# greenshield.net
KiCad netlist of a schematic drawn in EAGLE
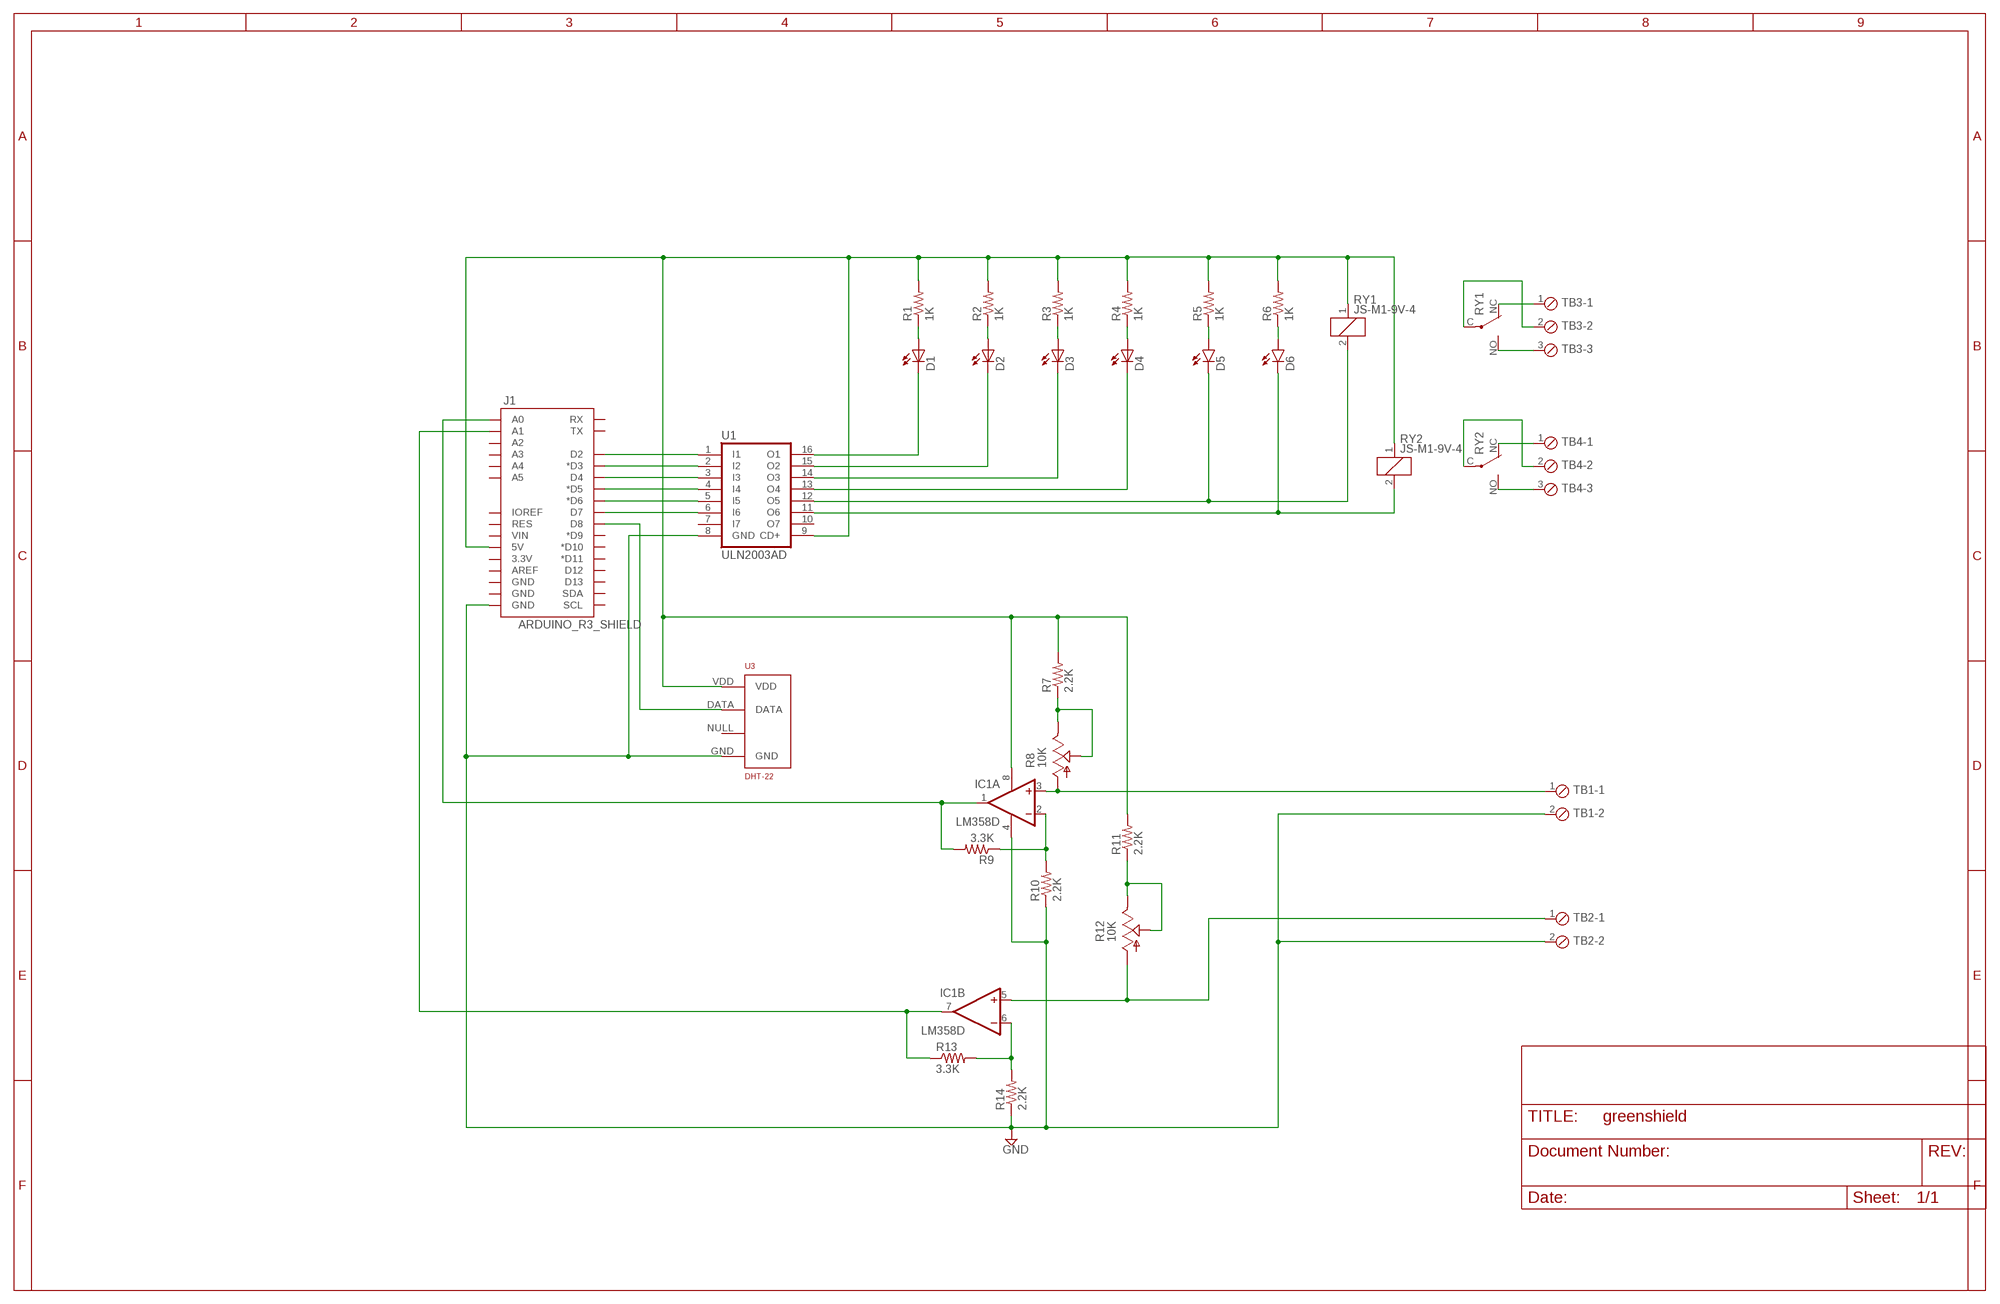
[diagram p0: schematic, sheet 1]

(export (version "E")
  (design (tool "Eeschema 10.0.6"))
  (components
    (comp (ref "D1")
      (value "LED3MM")
      (footprint "eagle-import:LED3MM")
      (libsource (lib "eagle-import") (part "led_LED3MM"))
    )
    (comp (ref "D2")
      (value "LED3MM")
      (footprint "eagle-import:LED3MM")
      (libsource (lib "eagle-import") (part "led_LED3MM"))
    )
    (comp (ref "D3")
      (value "LED3MM")
      (footprint "eagle-import:LED3MM")
      (libsource (lib "eagle-import") (part "led_LED3MM"))
    )
    (comp (ref "D4")
      (value "LED3MM")
      (footprint "eagle-import:LED3MM")
      (libsource (lib "eagle-import") (part "led_LED3MM"))
    )
    (comp (ref "D5")
      (value "LED3MM")
      (footprint "eagle-import:LED3MM")
      (libsource (lib "eagle-import") (part "LED3MM"))
    )
    (comp (ref "D6")
      (value "LED3MM")
      (footprint "eagle-import:LED3MM")
      (libsource (lib "eagle-import") (part "LED3MM"))
    )
    (comp (ref "IC1")
      (value "LM358D")
      (footprint "eagle-import:SO08")
      (libsource (lib "eagle-import") (part "LM358D"))
    )
    (comp (ref "J1")
      (value "ARDUINO_R3_SHIELD")
      (footprint "eagle-import:UNO_R3_SHIELD")
      (libsource (lib "eagle-import") (part "ARDUINO_R3_SHIELD"))
    )
    (comp (ref "R1")
      (value "1K")
      (footprint "eagle-import:0805")
      (libsource (lib "eagle-import") (part "RESISTOR0805-RES"))
    )
    (comp (ref "R2")
      (value "1K")
      (footprint "eagle-import:0805")
      (libsource (lib "eagle-import") (part "RESISTOR0805-RES"))
    )
    (comp (ref "R3")
      (value "1K")
      (footprint "eagle-import:0805")
      (libsource (lib "eagle-import") (part "RESISTOR0805-RES"))
    )
    (comp (ref "R4")
      (value "1K")
      (footprint "eagle-import:0805")
      (libsource (lib "eagle-import") (part "RESISTOR0805-RES"))
    )
    (comp (ref "R5")
      (value "1K")
      (footprint "eagle-import:0805")
      (libsource (lib "eagle-import") (part "RESISTOR0805-RES"))
    )
    (comp (ref "R6")
      (value "1K")
      (footprint "eagle-import:0805")
      (libsource (lib "eagle-import") (part "RESISTOR0805-RES"))
    )
    (comp (ref "R7")
      (value "2.2K")
      (footprint "eagle-import:0805")
      (libsource (lib "eagle-import") (part "RESISTOR0805-RES"))
    )
    (comp (ref "R8")
      (value "10K")
      (footprint "eagle-import:S64W")
      (libsource (lib "eagle-import") (part "TRIM_US-S64W"))
    )
    (comp (ref "R9")
      (value "3.3K")
      (footprint "eagle-import:0805")
      (libsource (lib "eagle-import") (part "RESISTOR0805-RES"))
    )
    (comp (ref "R10")
      (value "2.2K")
      (footprint "eagle-import:0805")
      (libsource (lib "eagle-import") (part "RESISTOR0805-RES"))
    )
    (comp (ref "R11")
      (value "2.2K")
      (footprint "eagle-import:0805")
      (libsource (lib "eagle-import") (part "RESISTOR0805-RES"))
    )
    (comp (ref "R12")
      (value "10K")
      (footprint "eagle-import:S64W")
      (libsource (lib "eagle-import") (part "TRIM_US-S64W"))
    )
    (comp (ref "R13")
      (value "3.3K")
      (footprint "eagle-import:0805")
      (libsource (lib "eagle-import") (part "RESISTOR0805-RES"))
    )
    (comp (ref "R14")
      (value "2.2K")
      (footprint "eagle-import:0805")
      (libsource (lib "eagle-import") (part "RESISTOR0805-RES"))
    )
    (comp (ref "RY1")
      (value "JS-M1-9V-4")
      (footprint "eagle-import:JS-M")
      (libsource (lib "eagle-import") (part "JS-M1-9V-4"))
    )
    (comp (ref "RY2")
      (value "JS-M1-9V-4")
      (footprint "eagle-import:JS-M")
      (libsource (lib "eagle-import") (part "JS-M1-9V-4"))
    )
    (comp (ref "TB1")
      (value "MPT2")
      (footprint "eagle-import:2POL254")
      (libsource (lib "eagle-import") (part "MPT2"))
    )
    (comp (ref "TB2")
      (value "MPT2")
      (footprint "eagle-import:2POL254")
      (libsource (lib "eagle-import") (part "MPT2"))
    )
    (comp (ref "TB3")
      (value "MPT3")
      (footprint "eagle-import:3POL254")
      (libsource (lib "eagle-import") (part "MPT3"))
    )
    (comp (ref "TB4")
      (value "MPT3")
      (footprint "eagle-import:3POL254")
      (libsource (lib "eagle-import") (part "MPT3"))
    )
    (comp (ref "U1")
      (value "ULN2003AD")
      (footprint "eagle-import:SO16")
      (libsource (lib "eagle-import") (part "ULN2003AD"))
    )
    (comp (ref "U3")
      (value "DHT-22")
      (footprint "eagle-import:RHT03_DHT-22")
      (libsource (lib "eagle-import") (part "RHT03_DHT-22_AM2302"))
    )
  )
  (nets
    (net (code "1") (name "GND") (class "Default")
      (node (ref "IC1") (pin "4") (pinfunction "V-_4") (pintype "power_in"))
      (node (ref "J1") (pin "GND@0") (pinfunction "GND_GND@0") (pintype "bidirectional"))
      (node (ref "R10") (pin "1") (pinfunction "1_1") (pintype "passive"))
      (node (ref "R14") (pin "1") (pinfunction "1_1") (pintype "passive"))
      (node (ref "TB1") (pin "2") (pinfunction "1_2") (pintype "passive"))
      (node (ref "TB2") (pin "2") (pinfunction "1_2") (pintype "passive"))
      (node (ref "U1") (pin "8") (pinfunction "GND_8") (pintype "power_in"))
      (node (ref "U3") (pin "GND") (pinfunction "GND_GND") (pintype "power_in"))
    )
    (net (code "2") (name "Net-(D1-C)") (class "Default")
      (node (ref "D1") (pin "K") (pinfunction "C_K") (pintype "passive"))
      (node (ref "U1") (pin "16") (pinfunction "O1_16") (pintype "open_collector"))
    )
    (net (code "3") (name "Net-(D1-PadA)") (class "Default")
      (node (ref "D1") (pin "A") (pinfunction "A_A") (pintype "passive"))
      (node (ref "R1") (pin "1") (pinfunction "1_1") (pintype "passive"))
    )
    (net (code "4") (name "Net-(D2-C)") (class "Default")
      (node (ref "D2") (pin "K") (pinfunction "C_K") (pintype "passive"))
      (node (ref "U1") (pin "15") (pinfunction "O2_15") (pintype "open_collector"))
    )
    (net (code "5") (name "Net-(D2-PadA)") (class "Default")
      (node (ref "D2") (pin "A") (pinfunction "A_A") (pintype "passive"))
      (node (ref "R2") (pin "1") (pinfunction "1_1") (pintype "passive"))
    )
    (net (code "6") (name "Net-(D3-C)") (class "Default")
      (node (ref "D3") (pin "K") (pinfunction "C_K") (pintype "passive"))
      (node (ref "U1") (pin "14") (pinfunction "O3_14") (pintype "open_collector"))
    )
    (net (code "7") (name "Net-(D3-PadA)") (class "Default")
      (node (ref "D3") (pin "A") (pinfunction "A_A") (pintype "passive"))
      (node (ref "R3") (pin "1") (pinfunction "1_1") (pintype "passive"))
    )
    (net (code "8") (name "Net-(D4-C)") (class "Default")
      (node (ref "D4") (pin "K") (pinfunction "C_K") (pintype "passive"))
      (node (ref "U1") (pin "13") (pinfunction "O4_13") (pintype "open_collector"))
    )
    (net (code "9") (name "Net-(D4-PadA)") (class "Default")
      (node (ref "D4") (pin "A") (pinfunction "A_A") (pintype "passive"))
      (node (ref "R4") (pin "1") (pinfunction "1_1") (pintype "passive"))
    )
    (net (code "10") (name "Net-(D5-C)") (class "Default")
      (node (ref "D5") (pin "K") (pinfunction "C_K") (pintype "passive"))
      (node (ref "RY1") (pin "2") (pinfunction "2_2") (pintype "passive"))
      (node (ref "U1") (pin "12") (pinfunction "O5_12") (pintype "open_collector"))
    )
    (net (code "11") (name "Net-(D5-PadA)") (class "Default")
      (node (ref "D5") (pin "A") (pinfunction "A_A") (pintype "passive"))
      (node (ref "R5") (pin "1") (pinfunction "1_1") (pintype "passive"))
    )
    (net (code "12") (name "Net-(D6-C)") (class "Default")
      (node (ref "D6") (pin "K") (pinfunction "C_K") (pintype "passive"))
      (node (ref "RY2") (pin "2") (pinfunction "2_2") (pintype "passive"))
      (node (ref "U1") (pin "11") (pinfunction "O6_11") (pintype "open_collector"))
    )
    (net (code "13") (name "Net-(D6-PadA)") (class "Default")
      (node (ref "D6") (pin "A") (pinfunction "A_A") (pintype "passive"))
      (node (ref "R6") (pin "1") (pinfunction "1_1") (pintype "passive"))
    )
    (net (code "14") (name "Net-(IC1A-+IN)") (class "Default")
      (node (ref "IC1") (pin "3") (pinfunction "+IN_3") (pintype "input"))
      (node (ref "R8") (pin "A") (pinfunction "A_A") (pintype "passive"))
      (node (ref "TB1") (pin "1") (pinfunction "1_1") (pintype "passive"))
    )
    (net (code "15") (name "Net-(IC1A--IN)") (class "Default")
      (node (ref "IC1") (pin "2") (pinfunction "-IN_2") (pintype "input"))
      (node (ref "R10") (pin "2") (pinfunction "2_2") (pintype "passive"))
      (node (ref "R9") (pin "1") (pinfunction "1_1") (pintype "passive"))
    )
    (net (code "16") (name "Net-(IC1A-OUT)") (class "Default")
      (node (ref "IC1") (pin "1") (pinfunction "OUT_1") (pintype "output"))
      (node (ref "J1") (pin "A0") (pinfunction "A0_A0") (pintype "bidirectional"))
      (node (ref "R9") (pin "2") (pinfunction "2_2") (pintype "passive"))
    )
    (net (code "17") (name "Net-(IC1B-+IN)") (class "Default")
      (node (ref "IC1") (pin "5") (pinfunction "+IN_5") (pintype "input"))
      (node (ref "R12") (pin "A") (pinfunction "A_A") (pintype "passive"))
      (node (ref "TB2") (pin "1") (pinfunction "1_1") (pintype "passive"))
    )
    (net (code "18") (name "Net-(IC1B--IN)") (class "Default")
      (node (ref "IC1") (pin "6") (pinfunction "-IN_6") (pintype "input"))
      (node (ref "R13") (pin "2") (pinfunction "2_2") (pintype "passive"))
      (node (ref "R14") (pin "2") (pinfunction "2_2") (pintype "passive"))
    )
    (net (code "19") (name "Net-(IC1B-OUT)") (class "Default")
      (node (ref "IC1") (pin "7") (pinfunction "OUT_7") (pintype "output"))
      (node (ref "J1") (pin "A1") (pinfunction "A1_A1") (pintype "bidirectional"))
      (node (ref "R13") (pin "1") (pinfunction "1_1") (pintype "passive"))
    )
    (net (code "20") (name "Net-(IC1C-V+)") (class "Default")
      (node (ref "IC1") (pin "8") (pinfunction "V+_8") (pintype "power_in"))
      (node (ref "J1") (pin "5V") (pinfunction "5V_5V") (pintype "bidirectional"))
      (node (ref "R1") (pin "2") (pinfunction "2_2") (pintype "passive"))
      (node (ref "R11") (pin "2") (pinfunction "2_2") (pintype "passive"))
      (node (ref "R2") (pin "2") (pinfunction "2_2") (pintype "passive"))
      (node (ref "R3") (pin "2") (pinfunction "2_2") (pintype "passive"))
      (node (ref "R4") (pin "2") (pinfunction "2_2") (pintype "passive"))
      (node (ref "R5") (pin "2") (pinfunction "2_2") (pintype "passive"))
      (node (ref "R6") (pin "2") (pinfunction "2_2") (pintype "passive"))
      (node (ref "R7") (pin "2") (pinfunction "2_2") (pintype "passive"))
      (node (ref "RY1") (pin "1") (pinfunction "1_1") (pintype "passive"))
      (node (ref "RY2") (pin "1") (pinfunction "1_1") (pintype "passive"))
      (node (ref "U1") (pin "9") (pinfunction "CD+_9") (pintype "passive"))
      (node (ref "U3") (pin "VDD") (pinfunction "VDD_VDD") (pintype "power_in"))
    )
    (net (code "21") (name "Net-(J1-*D3)") (class "Default")
      (node (ref "J1") (pin "D3") (pinfunction "*D3_D3") (pintype "bidirectional"))
      (node (ref "U1") (pin "2") (pinfunction "I2_2") (pintype "input"))
    )
    (net (code "22") (name "Net-(J1-*D5)") (class "Default")
      (node (ref "J1") (pin "D5") (pinfunction "*D5_D5") (pintype "bidirectional"))
      (node (ref "U1") (pin "4") (pinfunction "I4_4") (pintype "input"))
    )
    (net (code "23") (name "Net-(J1-*D6)") (class "Default")
      (node (ref "J1") (pin "D6") (pinfunction "*D6_D6") (pintype "bidirectional"))
      (node (ref "U1") (pin "5") (pinfunction "I5_5") (pintype "input"))
    )
    (net (code "24") (name "Net-(J1-PadD8)") (class "Default")
      (node (ref "J1") (pin "D8") (pinfunction "D8_D8") (pintype "bidirectional"))
      (node (ref "U3") (pin "DATA") (pinfunction "DATA_DATA") (pintype "bidirectional"))
    )
    (net (code "25") (name "Net-(R7-Pad1)") (class "Default")
      (node (ref "R7") (pin "1") (pinfunction "1_1") (pintype "passive"))
      (node (ref "R8") (pin "E") (pinfunction "E_E") (pintype "passive"))
      (node (ref "R8") (pin "S") (pinfunction "S_S") (pintype "passive"))
    )
    (net (code "26") (name "Net-(R11-Pad1)") (class "Default")
      (node (ref "R11") (pin "1") (pinfunction "1_1") (pintype "passive"))
      (node (ref "R12") (pin "E") (pinfunction "E_E") (pintype "passive"))
      (node (ref "R12") (pin "S") (pinfunction "S_S") (pintype "passive"))
    )
    (net (code "27") (name "Net-(RY1B-O)") (class "Default")
      (node (ref "RY1") (pin "NC") (pinfunction "O_NC") (pintype "passive"))
      (node (ref "TB3") (pin "1") (pinfunction "1_1") (pintype "passive"))
    )
    (net (code "28") (name "Net-(RY1B-P)") (class "Default")
      (node (ref "RY1") (pin "C") (pinfunction "P_C") (pintype "passive"))
      (node (ref "TB3") (pin "2") (pinfunction "1_2") (pintype "passive"))
    )
    (net (code "29") (name "Net-(RY1B-S)") (class "Default")
      (node (ref "RY1") (pin "NO") (pinfunction "S_NO") (pintype "passive"))
      (node (ref "TB3") (pin "3") (pinfunction "1_3") (pintype "passive"))
    )
    (net (code "30") (name "Net-(RY2B-O)") (class "Default")
      (node (ref "RY2") (pin "NC") (pinfunction "O_NC") (pintype "passive"))
      (node (ref "TB4") (pin "1") (pinfunction "1_1") (pintype "passive"))
    )
    (net (code "31") (name "Net-(RY2B-P)") (class "Default")
      (node (ref "RY2") (pin "C") (pinfunction "P_C") (pintype "passive"))
      (node (ref "TB4") (pin "2") (pinfunction "1_2") (pintype "passive"))
    )
    (net (code "32") (name "Net-(RY2B-S)") (class "Default")
      (node (ref "RY2") (pin "NO") (pinfunction "S_NO") (pintype "passive"))
      (node (ref "TB4") (pin "3") (pinfunction "1_3") (pintype "passive"))
    )
    (net (code "33") (name "Net-(U1-I1)") (class "Default")
      (node (ref "J1") (pin "D2") (pinfunction "D2_D2") (pintype "bidirectional"))
      (node (ref "U1") (pin "1") (pinfunction "I1_1") (pintype "input"))
    )
    (net (code "34") (name "Net-(U1-I3)") (class "Default")
      (node (ref "J1") (pin "D4") (pinfunction "D4_D4") (pintype "bidirectional"))
      (node (ref "U1") (pin "3") (pinfunction "I3_3") (pintype "input"))
    )
    (net (code "35") (name "Net-(U1-I6)") (class "Default")
      (node (ref "J1") (pin "D7") (pinfunction "D7_D7") (pintype "bidirectional"))
      (node (ref "U1") (pin "6") (pinfunction "I6_6") (pintype "input"))
    )
    (net (code "36") (name "unconnected-(J1-*D9-PadD9)") (class "Default")
      (node (ref "J1") (pin "D9") (pinfunction "*D9_D9") (pintype "bidirectional"))
    )
    (net (code "37") (name "unconnected-(J1-*D10-PadD10)") (class "Default")
      (node (ref "J1") (pin "D10") (pinfunction "*D10_D10") (pintype "bidirectional"))
    )
    (net (code "38") (name "unconnected-(J1-*D11-PadD11)") (class "Default")
      (node (ref "J1") (pin "D11") (pinfunction "*D11_D11") (pintype "bidirectional"))
    )
    (net (code "39") (name "unconnected-(J1-GND-PadGND@1)") (class "Default")
      (node (ref "J1") (pin "GND@1") (pinfunction "GND_GND@1") (pintype "bidirectional"))
    )
    (net (code "40") (name "unconnected-(J1-GND-PadGND@2)") (class "Default")
      (node (ref "J1") (pin "GND@2") (pinfunction "GND_GND@2") (pintype "bidirectional"))
    )
    (net (code "41") (name "unconnected-(J1-Pad3.3V)") (class "Default")
      (node (ref "J1") (pin "3.3V") (pinfunction "3.3V_3.3V") (pintype "bidirectional"))
    )
    (net (code "42") (name "unconnected-(J1-PadA2)") (class "Default")
      (node (ref "J1") (pin "A2") (pinfunction "A2_A2") (pintype "bidirectional"))
    )
    (net (code "43") (name "unconnected-(J1-PadA3)") (class "Default")
      (node (ref "J1") (pin "A3") (pinfunction "A3_A3") (pintype "bidirectional"))
    )
    (net (code "44") (name "unconnected-(J1-PadA4)") (class "Default")
      (node (ref "J1") (pin "A4") (pinfunction "A4_A4") (pintype "bidirectional"))
    )
    (net (code "45") (name "unconnected-(J1-PadA5)") (class "Default")
      (node (ref "J1") (pin "A5") (pinfunction "A5_A5") (pintype "bidirectional"))
    )
    (net (code "46") (name "unconnected-(J1-PadAREF)") (class "Default")
      (node (ref "J1") (pin "AREF") (pinfunction "AREF_AREF") (pintype "bidirectional"))
    )
    (net (code "47") (name "unconnected-(J1-PadD12)") (class "Default")
      (node (ref "J1") (pin "D12") (pinfunction "D12_D12") (pintype "bidirectional"))
    )
    (net (code "48") (name "unconnected-(J1-PadD13)") (class "Default")
      (node (ref "J1") (pin "D13") (pinfunction "D13_D13") (pintype "bidirectional"))
    )
    (net (code "49") (name "unconnected-(J1-PadIOREF)") (class "Default")
      (node (ref "J1") (pin "IOREF") (pinfunction "IOREF_IOREF") (pintype "bidirectional"))
    )
    (net (code "50") (name "unconnected-(J1-PadRES)") (class "Default")
      (node (ref "J1") (pin "RES") (pinfunction "RES_RES") (pintype "bidirectional"))
    )
    (net (code "51") (name "unconnected-(J1-PadRX)") (class "Default")
      (node (ref "J1") (pin "RX") (pinfunction "RX_RX") (pintype "bidirectional"))
    )
    (net (code "52") (name "unconnected-(J1-PadSCL)") (class "Default")
      (node (ref "J1") (pin "SCL") (pinfunction "SCL_SCL") (pintype "bidirectional"))
    )
    (net (code "53") (name "unconnected-(J1-PadSDA)") (class "Default")
      (node (ref "J1") (pin "SDA") (pinfunction "SDA_SDA") (pintype "bidirectional"))
    )
    (net (code "54") (name "unconnected-(J1-PadTX)") (class "Default")
      (node (ref "J1") (pin "TX") (pinfunction "TX_TX") (pintype "bidirectional"))
    )
    (net (code "55") (name "unconnected-(J1-PadVIN)") (class "Default")
      (node (ref "J1") (pin "VIN") (pinfunction "VIN_VIN") (pintype "bidirectional"))
    )
    (net (code "56") (name "unconnected-(U1-I7-Pad7)") (class "Default")
      (node (ref "U1") (pin "7") (pinfunction "I7_7") (pintype "input"))
    )
    (net (code "57") (name "unconnected-(U1-O7-Pad10)") (class "Default")
      (node (ref "U1") (pin "10") (pinfunction "O7_10") (pintype "open_collector"))
    )
    (net (code "58") (name "unconnected-(U3-PadNULL)") (class "Default")
      (node (ref "U3") (pin "NULL") (pinfunction "NULL_NULL") (pintype "no_connect"))
    )
  )
)
